# TOP.net
KiCad netlist of a schematic drawn in Altium Designer
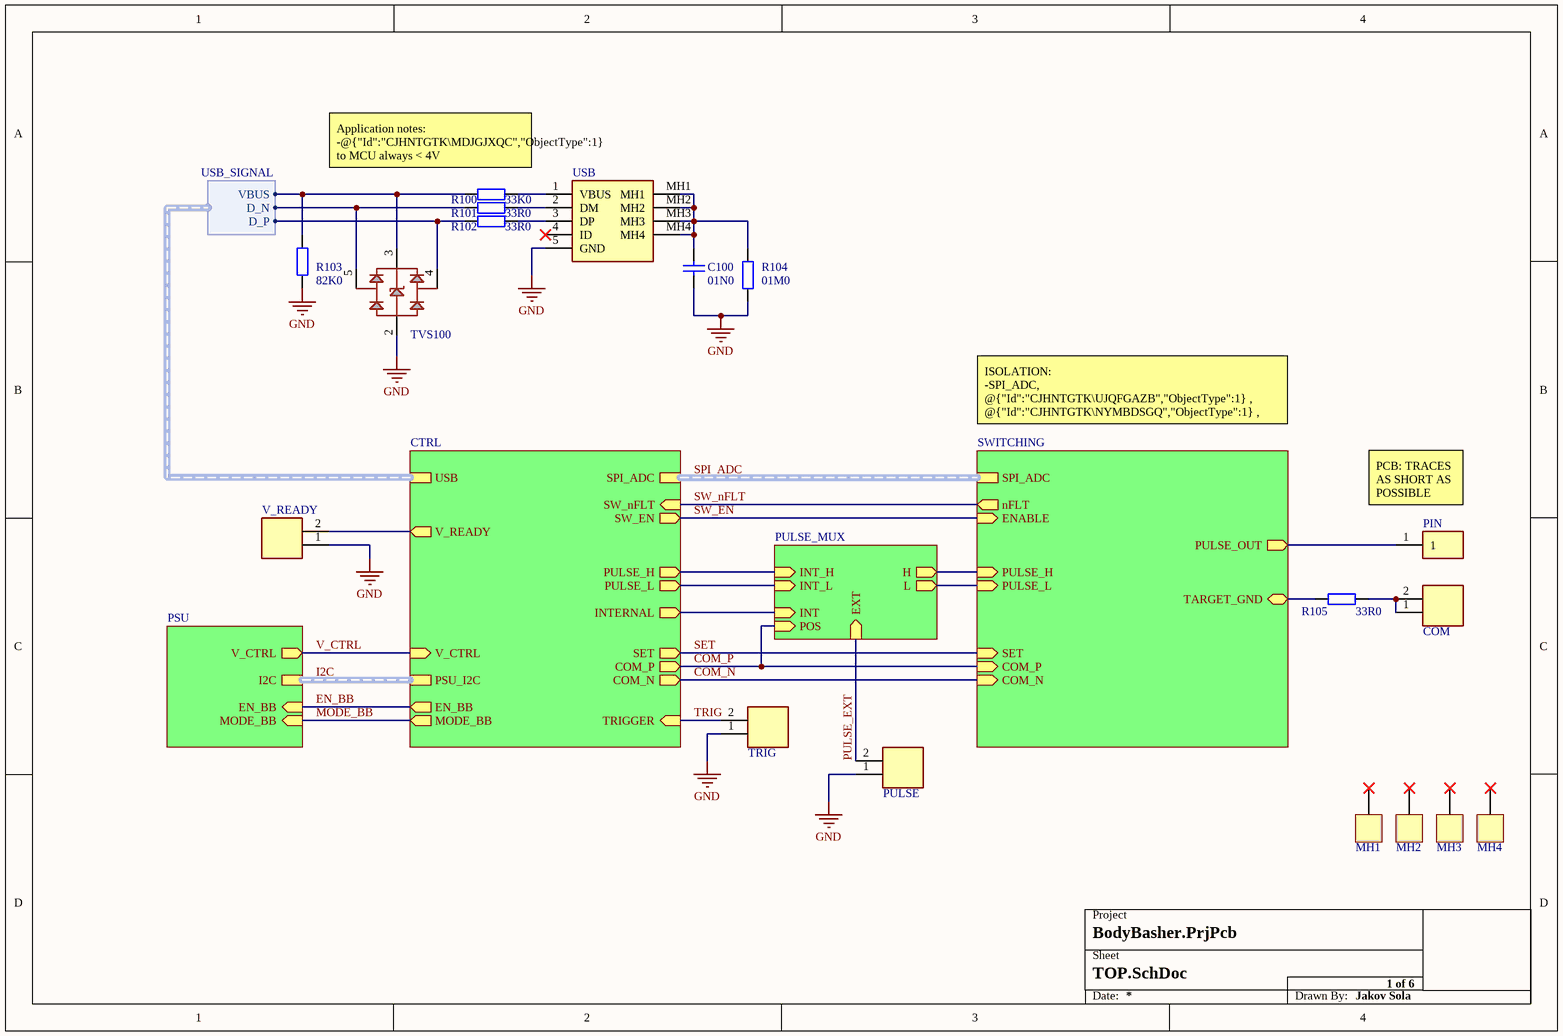
[diagram p0: TOP.SchDoc]

(export (version "E")
  (design (tool "Eeschema 10.0.6"))
  (components
    (comp (ref "C100")
      (value "Cap")
      (footprint "CAPC0805N")
      (fields
        (field (name "VALUE_4C") "01N0")
        (field (name "VOLTAGE") "100V")
        (field (name "TOLERANCE") "0.1")
      )
      (libsource (lib "Capacitors") (part "Cap"))
    )
    (comp (ref "COM")
      (value "CON_2P")
      (footprint "2MMHBS02VT02HTB")
      (libsource (lib "Other_passive") (part "CON_2P"))
    )
    (comp (ref "MH1") (value "MH") (footprint "MH") (libsource (lib "Other_passive") (part "MH")))
    (comp (ref "MH2") (value "MH") (footprint "MH") (libsource (lib "Other_passive") (part "MH")))
    (comp (ref "MH3") (value "MH") (footprint "MH") (libsource (lib "Other_passive") (part "MH")))
    (comp (ref "MH4") (value "MH") (footprint "MH") (libsource (lib "Other_passive") (part "MH")))
    (comp (ref "PIN") (value "CON_1P") (footprint "POGO") (libsource (lib "Other_passive") (part "CON_1P")))
    (comp (ref "PULSE")
      (value "CON_2P")
      (footprint "2MMHBS02VT02HTB")
      (libsource (lib "Other_passive") (part "CON_2P"))
    )
    (comp (ref "R100")
      (value "Res")
      (footprint "RESC0603N")
      (description "Resistor")
      (fields (field (name "VALUE_4C") "33K0") (field (name "POWER") "0.1W") (field (name "TOLERANCE") "1%"))
      (libsource (lib "") (part "Res_2"))
    )
    (comp (ref "R101")
      (value "Res")
      (footprint "RESC0603N")
      (description "Resistor")
      (fields (field (name "VALUE_4C") "33R0") (field (name "POWER") "0.1W") (field (name "TOLERANCE") "1%"))
      (libsource (lib "Resistors") (part "Res"))
    )
    (comp (ref "R102")
      (value "Res")
      (footprint "RESC0603N")
      (description "Resistor")
      (fields (field (name "VALUE_4C") "33R0") (field (name "POWER") "0.1W") (field (name "TOLERANCE") "1%"))
      (libsource (lib "Resistors") (part "Res"))
    )
    (comp (ref "R103")
      (value "Res")
      (footprint "RESC0603N")
      (description "Resistor")
      (fields (field (name "VALUE_4C") "82K0") (field (name "POWER") "0.1W") (field (name "TOLERANCE") "1%"))
      (libsource (lib "") (part "Res_1"))
    )
    (comp (ref "R104")
      (value "Res")
      (footprint "RESC0603N")
      (description "Resistor")
      (fields
        (field (name "VALUE_4C") "01M0")
        (field (name "POWER") "0.063W")
        (field (name "TOLERANCE") "1%")
      )
      (libsource (lib "") (part "Res_1"))
    )
    (comp (ref "R105")
      (value "Res")
      (footprint "RESC0603N")
      (description "Resistor")
      (fields (field (name "VALUE_4C") "33R0") (field (name "POWER") "0.1W") (field (name "TOLERANCE") "1%"))
      (libsource (lib "Resistors") (part "Res"))
    )
    (comp (ref "TRIG")
      (value "CON_2P")
      (footprint "2MMHBS02VT02HTB")
      (libsource (lib "Other_passive") (part "CON_2P"))
    )
    (comp (ref "TVS100")
      (value "SP3003_2X")
      (footprint "SC70_5")
      (libsource (lib "Diodes") (part "SP3003_2X"))
    )
    (comp (ref "USB")
      (value "microUSB_CON")
      (footprint "476420001")
      (libsource (lib "Other_passive") (part "microUSB_CON"))
    )
    (comp (ref "V_READY")
      (value "CON_2P")
      (footprint "2MMHBS02VT02HTB")
      (libsource (lib "") (part "CON_2P_1"))
    )
  )
  (nets
    (net (code "11") (name "/PULSE_EXT") (class "Default")
      (node (ref "PULSE") (pin "2") (pinfunction "2_2") (pintype "passive"))
    )
    (net (code "14") (name "/PULSE_OUT") (class "Default")
      (node (ref "PIN") (pin "1") (pinfunction "1_1") (pintype "passive"))
    )
    (net (code "18") (name "/TARGET_GND") (class "Default")
      (node (ref "R105") (pin "1") (pinfunction "1_1") (pintype "passive"))
    )
    (net (code "19") (name "/TRIG") (class "Default")
      (node (ref "TRIG") (pin "2") (pinfunction "2_2") (pintype "passive"))
    )
    (net (code "21") (name "/V_READY") (class "Default")
      (node (ref "V_READY") (pin "2") (pinfunction "2_2") (pintype "passive"))
    )
    (net (code "25") (name "GND") (class "Default")
      (node (ref "C100") (pin "1") (pinfunction "1_1") (pintype "passive"))
      (node (ref "PULSE") (pin "1") (pinfunction "1_1") (pintype "passive"))
      (node (ref "R103") (pin "1") (pinfunction "1_1") (pintype "passive"))
      (node (ref "R104") (pin "1") (pinfunction "1_1") (pintype "passive"))
      (node (ref "TRIG") (pin "1") (pinfunction "1_1") (pintype "passive"))
      (node (ref "TVS100") (pin "2") (pinfunction "2_2") (pintype "passive"))
      (node (ref "USB") (pin "5") (pinfunction "GND_5") (pintype "passive"))
      (node (ref "V_READY") (pin "1") (pinfunction "1_1") (pintype "passive"))
    )
    (net (code "26") (name "Net-(C100-Pad2)") (class "Default")
      (node (ref "C100") (pin "2") (pinfunction "2_2") (pintype "passive"))
      (node (ref "R104") (pin "2") (pinfunction "2_2") (pintype "passive"))
      (node (ref "USB") (pin "MH1") (pinfunction "MH1_MH1") (pintype "passive"))
      (node (ref "USB") (pin "MH2") (pinfunction "MH2_MH2") (pintype "passive"))
      (node (ref "USB") (pin "MH3") (pinfunction "MH3_MH3") (pintype "passive"))
      (node (ref "USB") (pin "MH4") (pinfunction "MH4_MH4") (pintype "passive"))
    )
    (net (code "27") (name "Net-(COM-Pad1)") (class "Default")
      (node (ref "COM") (pin "1") (pinfunction "1_1") (pintype "passive"))
      (node (ref "COM") (pin "2") (pinfunction "2_2") (pintype "passive"))
      (node (ref "R105") (pin "2") (pinfunction "2_2") (pintype "passive"))
    )
    (net (code "28") (name "Net-(R100-Pad2)") (class "Default")
      (node (ref "R100") (pin "2") (pinfunction "2_2") (pintype "passive"))
      (node (ref "R103") (pin "2") (pinfunction "2_2") (pintype "passive"))
      (node (ref "TVS100") (pin "3") (pinfunction "3_3") (pintype "passive"))
    )
    (net (code "29") (name "Net-(R101-Pad1)") (class "Default")
      (node (ref "R101") (pin "1") (pinfunction "1_1") (pintype "passive"))
      (node (ref "TVS100") (pin "5") (pinfunction "5_5") (pintype "passive"))
    )
    (net (code "30") (name "Net-(R102-Pad1)") (class "Default")
      (node (ref "R102") (pin "1") (pinfunction "1_1") (pintype "passive"))
      (node (ref "TVS100") (pin "4") (pinfunction "4_4") (pintype "passive"))
    )
    (net (code "31") (name "Net-(USB-DM)") (class "Default")
      (node (ref "R101") (pin "2") (pinfunction "2_2") (pintype "passive"))
      (node (ref "USB") (pin "2") (pinfunction "DM_2") (pintype "passive"))
    )
    (net (code "32") (name "Net-(USB-DP)") (class "Default")
      (node (ref "R102") (pin "2") (pinfunction "2_2") (pintype "passive"))
      (node (ref "USB") (pin "3") (pinfunction "DP_3") (pintype "passive"))
    )
    (net (code "33") (name "Net-(USB-VBUS)") (class "Default")
      (node (ref "R100") (pin "1") (pinfunction "1_1") (pintype "passive"))
      (node (ref "USB") (pin "1") (pinfunction "VBUS_1") (pintype "passive"))
    )
    (net (code "34") (name "unconnected-(MH1-MH-Pad0)") (class "Default")
      (node (ref "MH1") (pin "0") (pinfunction "MH_0") (pintype "passive+no_connect"))
    )
    (net (code "35") (name "unconnected-(MH2-MH-Pad0)") (class "Default")
      (node (ref "MH2") (pin "0") (pinfunction "MH_0") (pintype "passive+no_connect"))
    )
    (net (code "36") (name "unconnected-(MH3-MH-Pad0)") (class "Default")
      (node (ref "MH3") (pin "0") (pinfunction "MH_0") (pintype "passive+no_connect"))
    )
    (net (code "37") (name "unconnected-(MH4-MH-Pad0)") (class "Default")
      (node (ref "MH4") (pin "0") (pinfunction "MH_0") (pintype "passive+no_connect"))
    )
    (net (code "38") (name "unconnected-(USB-ID-Pad4)") (class "Default")
      (node (ref "USB") (pin "4") (pinfunction "ID_4") (pintype "passive+no_connect"))
    )
  )
)
